# RF_TransimpedanceAmp_FDS02.net
KiCad netlist of a schematic drawn in EAGLE
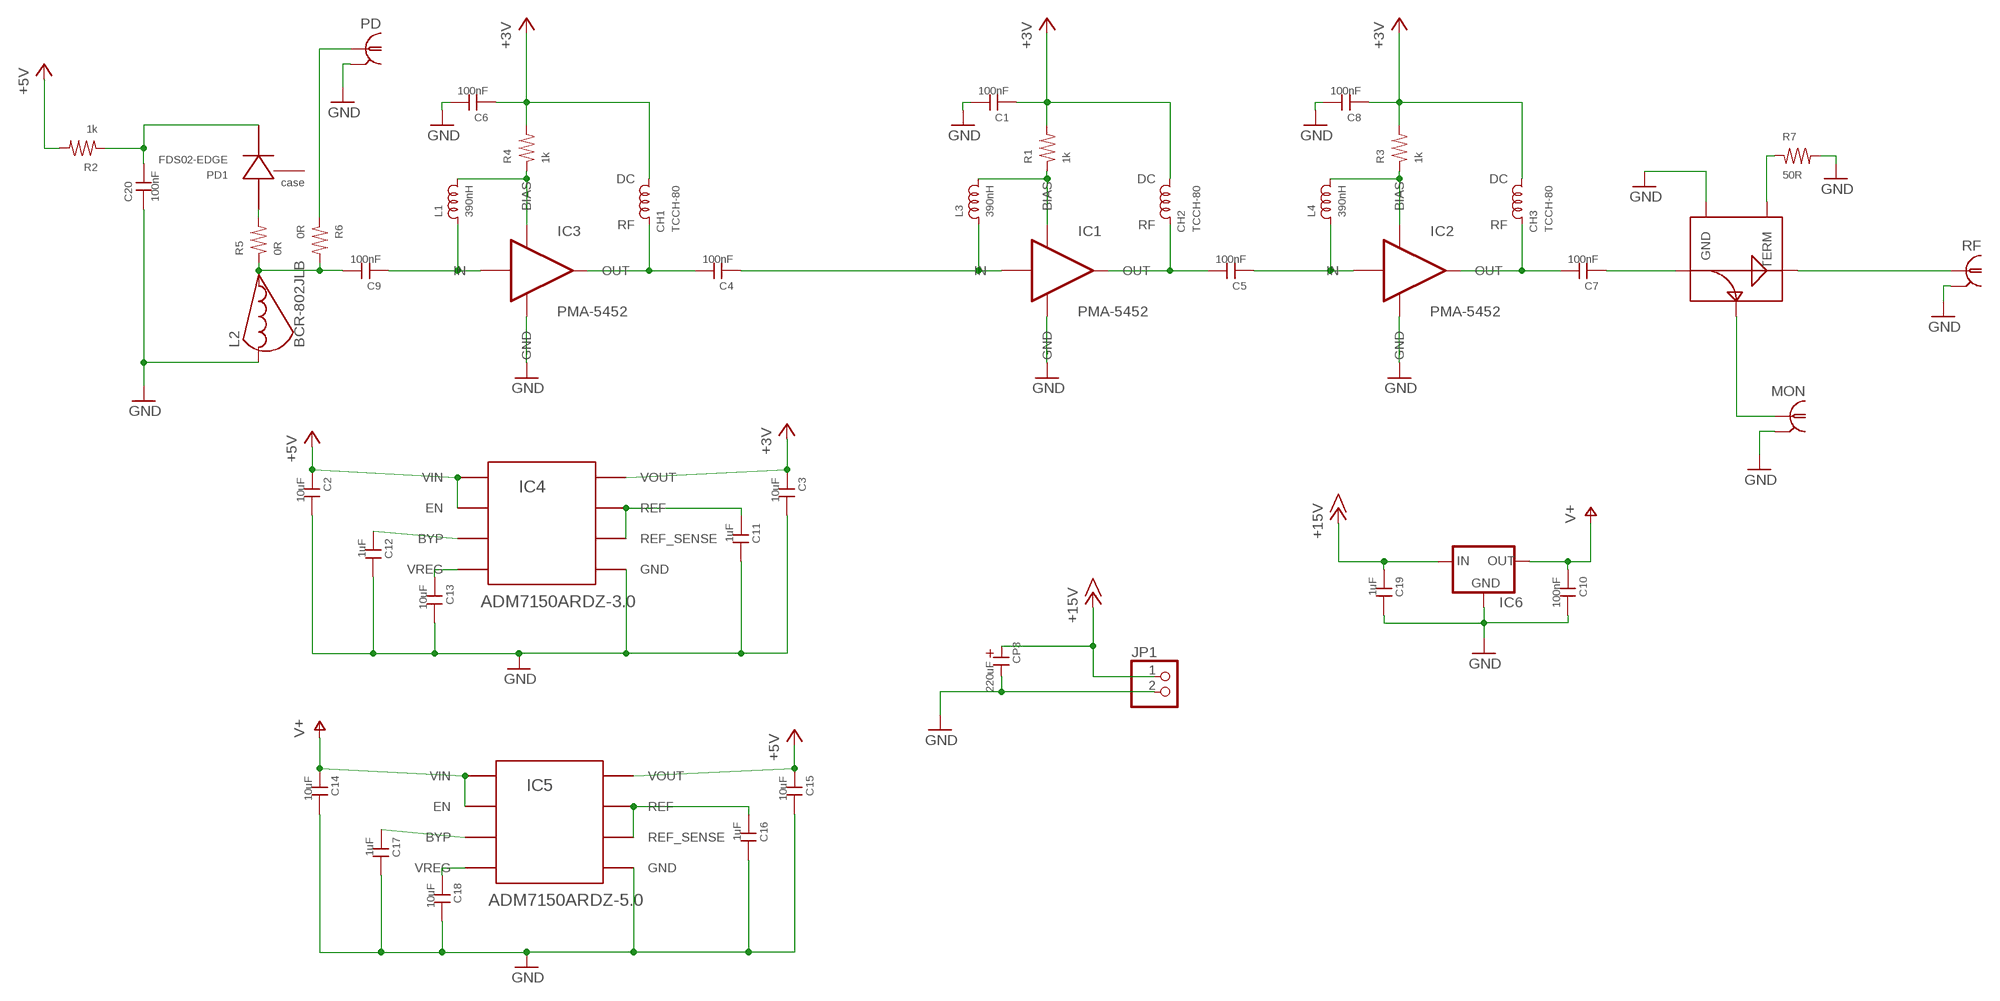
[diagram p0: schematic, sheet 1]

(export (version "E")
  (design (tool "Eeschema 10.0.6"))
  (components
    (comp (ref "C1")
      (value "100nF")
      (footprint "eagle-import:0402")
      (libsource (lib "eagle-import") (part "CAP0402"))
    )
    (comp (ref "C2")
      (value "10uF")
      (footprint "eagle-import:1210")
      (libsource (lib "eagle-import") (part "CAP1210"))
    )
    (comp (ref "C3")
      (value "10uF")
      (footprint "eagle-import:1210")
      (libsource (lib "eagle-import") (part "CAP1210"))
    )
    (comp (ref "C4")
      (value "100nF")
      (footprint "eagle-import:0402")
      (libsource (lib "eagle-import") (part "CAP0402"))
    )
    (comp (ref "C5")
      (value "100nF")
      (footprint "eagle-import:0402")
      (libsource (lib "eagle-import") (part "CAP0402"))
    )
    (comp (ref "C6")
      (value "100nF")
      (footprint "eagle-import:0402")
      (libsource (lib "eagle-import") (part "CAP0402"))
    )
    (comp (ref "C7")
      (value "100nF")
      (footprint "eagle-import:0402")
      (libsource (lib "eagle-import") (part "CAP0402"))
    )
    (comp (ref "C8")
      (value "100nF")
      (footprint "eagle-import:0402")
      (libsource (lib "eagle-import") (part "CAP0402"))
    )
    (comp (ref "C9")
      (value "100nF")
      (footprint "eagle-import:0402")
      (libsource (lib "eagle-import") (part "CAP0402"))
    )
    (comp (ref "C10")
      (value "100nF")
      (footprint "eagle-import:0603")
      (libsource (lib "eagle-import") (part "CAP0603"))
    )
    (comp (ref "C11")
      (value "1uF")
      (footprint "eagle-import:0603")
      (libsource (lib "eagle-import") (part "CAP0603"))
    )
    (comp (ref "C12")
      (value "1uF")
      (footprint "eagle-import:0603")
      (libsource (lib "eagle-import") (part "CAP0603"))
    )
    (comp (ref "C13")
      (value "10uF")
      (footprint "eagle-import:1210")
      (libsource (lib "eagle-import") (part "CAP1210"))
    )
    (comp (ref "C14")
      (value "10uF")
      (footprint "eagle-import:1210")
      (libsource (lib "eagle-import") (part "CAP1210"))
    )
    (comp (ref "C15")
      (value "10uF")
      (footprint "eagle-import:1210")
      (libsource (lib "eagle-import") (part "CAP1210"))
    )
    (comp (ref "C16")
      (value "1uF")
      (footprint "eagle-import:0603")
      (libsource (lib "eagle-import") (part "CAP0603"))
    )
    (comp (ref "C17")
      (value "1uF")
      (footprint "eagle-import:0603")
      (libsource (lib "eagle-import") (part "CAP0603"))
    )
    (comp (ref "C18")
      (value "10uF")
      (footprint "eagle-import:1210")
      (libsource (lib "eagle-import") (part "CAP1210"))
    )
    (comp (ref "C19")
      (value "1uF")
      (footprint "eagle-import:0603")
      (libsource (lib "eagle-import") (part "CAP0603"))
    )
    (comp (ref "C20")
      (value "100nF")
      (footprint "eagle-import:0402")
      (libsource (lib "eagle-import") (part "CAP0402"))
    )
    (comp (ref "CH1")
      (value "TCCH-80")
      (footprint "eagle-import:GU1604")
      (libsource (lib "eagle-import") (part "TCCH-80"))
    )
    (comp (ref "CH2")
      (value "TCCH-80")
      (footprint "eagle-import:GU1604")
      (libsource (lib "eagle-import") (part "TCCH-80"))
    )
    (comp (ref "CH3")
      (value "TCCH-80")
      (footprint "eagle-import:GU1604")
      (libsource (lib "eagle-import") (part "TCCH-80"))
    )
    (comp (ref "CP3")
      (value "220uF")
      (footprint "eagle-import:PANASONIC_F")
      (libsource (lib "eagle-import") (part "CAP-POLPANASONIC_F"))
    )
    (comp (ref "IC1")
      (value "PMA-5452")
      (footprint "eagle-import:DQ849")
      (libsource (lib "eagle-import") (part "PMA-5452"))
    )
    (comp (ref "IC2")
      (value "PMA-5452")
      (footprint "eagle-import:DQ849")
      (libsource (lib "eagle-import") (part "PMA-5452"))
    )
    (comp (ref "IC3")
      (value "PMA-5452")
      (footprint "eagle-import:DQ849")
      (libsource (lib "eagle-import") (part "PMA-5452"))
    )
    (comp (ref "IC4")
      (value "ADM7150ARDZ-3.0")
      (footprint "eagle-import:SO08")
      (libsource (lib "eagle-import") (part "ADM7150"))
    )
    (comp (ref "IC5")
      (value "ADM7150ARDZ-5.0")
      (footprint "eagle-import:SO08")
      (libsource (lib "eagle-import") (part "ADM7150"))
    )
    (comp (ref "IC6")
      (value "78XX-TO220")
      (footprint "eagle-import:TO220")
      (libsource (lib "eagle-import") (part "78XX-TO220"))
    )
    (comp (ref "JP1")
      (value "PINHD-1X2")
      (footprint "eagle-import:1X02")
      (libsource (lib "eagle-import") (part "PINHD-1X2"))
    )
    (comp (ref "L1")
      (value "390nH")
      (footprint "eagle-import:0402")
      (libsource (lib "eagle-import") (part "INDUCTOR-0402"))
    )
    (comp (ref "L2")
      (value "BCR-802JLB")
      (footprint "eagle-import:BCR-MED")
      (libsource (lib "eagle-import") (part "BCR-802JLB"))
    )
    (comp (ref "L3")
      (value "390nH")
      (footprint "eagle-import:0402")
      (libsource (lib "eagle-import") (part "INDUCTOR-0402"))
    )
    (comp (ref "L4")
      (value "390nH")
      (footprint "eagle-import:0402")
      (libsource (lib "eagle-import") (part "INDUCTOR-0402"))
    )
    (comp (ref "MON")
      (value "SMAJ502-bulkhead")
      (footprint "eagle-import:SMA-EDGE")
      (fields (field (name "PARTNO") "CONSMA006.062-ND"))
      (libsource (lib "eagle-import") (part "SMAJ502"))
    )
    (comp (ref "PD")
      (value "SMAJ502-bulkhead")
      (footprint "eagle-import:SMA-EDGE")
      (fields (field (name "PARTNO") "CONSMA006.062-ND"))
      (libsource (lib "eagle-import") (part "SMAJ502"))
    )
    (comp (ref "PD1")
      (value "FDS02-EDGE")
      (footprint "eagle-import:FDS02-SIDEMOUNT")
      (libsource (lib "eagle-import") (part "FDS02-EDGE"))
    )
    (comp (ref "R1")
      (value "1k")
      (footprint "eagle-import:0402")
      (libsource (lib "eagle-import") (part "RES0402"))
    )
    (comp (ref "R2")
      (value "1k")
      (footprint "eagle-import:0402")
      (libsource (lib "eagle-import") (part "RES0402"))
    )
    (comp (ref "R3")
      (value "1k")
      (footprint "eagle-import:0402")
      (libsource (lib "eagle-import") (part "RES0402"))
    )
    (comp (ref "R4")
      (value "1k")
      (footprint "eagle-import:0402")
      (libsource (lib "eagle-import") (part "RES0402"))
    )
    (comp (ref "R5")
      (value "0R")
      (footprint "eagle-import:0402")
      (libsource (lib "eagle-import") (part "RES0402"))
    )
    (comp (ref "R6")
      (value "0R")
      (footprint "eagle-import:0402")
      (libsource (lib "eagle-import") (part "RES0402"))
    )
    (comp (ref "R7")
      (value "50R")
      (footprint "eagle-import:0603")
      (libsource (lib "eagle-import") (part "RES0603"))
    )
    (comp (ref "RF")
      (value "SMAJ502")
      (footprint "eagle-import:SMA-EDGE")
      (libsource (lib "eagle-import") (part "SMAJ502"))
    )
    (comp (ref "U$1")
      (value "ADC-10-4")
      (footprint "eagle-import:BH292")
      (libsource (lib "eagle-import") (part "ADC-10-4"))
    )
  )
  (nets
    (net (code "1") (name "+3V") (class "Default")
      (node (ref "C1") (pin "1") (pinfunction "P$1_1") (pintype "passive"))
      (node (ref "C3") (pin "1") (pinfunction "P$1_1") (pintype "passive"))
      (node (ref "C6") (pin "1") (pinfunction "P$1_1") (pintype "passive"))
      (node (ref "C8") (pin "1") (pinfunction "P$1_1") (pintype "passive"))
      (node (ref "CH1") (pin "P$3") (pinfunction "DC_P$3") (pintype "passive"))
      (node (ref "CH2") (pin "P$3") (pinfunction "DC_P$3") (pintype "passive"))
      (node (ref "CH3") (pin "P$3") (pinfunction "DC_P$3") (pintype "passive"))
      (node (ref "IC4") (pin "2") (pinfunction "VOUT_2") (pintype "bidirectional"))
      (node (ref "R1") (pin "2") (pinfunction "P$2_2") (pintype "passive"))
      (node (ref "R3") (pin "2") (pinfunction "P$2_2") (pintype "passive"))
      (node (ref "R4") (pin "2") (pinfunction "P$2_2") (pintype "passive"))
    )
    (net (code "2") (name "+5V") (class "Default")
      (node (ref "C15") (pin "1") (pinfunction "P$1_1") (pintype "passive"))
      (node (ref "C2") (pin "1") (pinfunction "P$1_1") (pintype "passive"))
      (node (ref "IC4") (pin "7") (pinfunction "EN_7") (pintype "bidirectional"))
      (node (ref "IC4") (pin "8") (pinfunction "VIN_8") (pintype "bidirectional"))
      (node (ref "IC5") (pin "2") (pinfunction "VOUT_2") (pintype "bidirectional"))
      (node (ref "R2") (pin "2") (pinfunction "P$2_2") (pintype "passive"))
    )
    (net (code "3") (name "+15V") (class "Default")
      (node (ref "C19") (pin "1") (pinfunction "P$1_1") (pintype "passive"))
      (node (ref "CP3") (pin "+") (pinfunction "P$1_+") (pintype "passive"))
      (node (ref "IC6") (pin "1") (pinfunction "IN_1") (pintype "input"))
      (node (ref "JP1") (pin "1") (pinfunction "1_1") (pintype "passive"))
    )
    (net (code "4") (name "GND") (class "Default")
      (node (ref "C1") (pin "2") (pinfunction "P$2_2") (pintype "passive"))
      (node (ref "C10") (pin "2") (pinfunction "P$2_2") (pintype "passive"))
      (node (ref "C11") (pin "2") (pinfunction "P$2_2") (pintype "passive"))
      (node (ref "C12") (pin "2") (pinfunction "P$2_2") (pintype "passive"))
      (node (ref "C13") (pin "2") (pinfunction "P$2_2") (pintype "passive"))
      (node (ref "C14") (pin "2") (pinfunction "P$2_2") (pintype "passive"))
      (node (ref "C15") (pin "2") (pinfunction "P$2_2") (pintype "passive"))
      (node (ref "C16") (pin "2") (pinfunction "P$2_2") (pintype "passive"))
      (node (ref "C17") (pin "2") (pinfunction "P$2_2") (pintype "passive"))
      (node (ref "C18") (pin "2") (pinfunction "P$2_2") (pintype "passive"))
      (node (ref "C19") (pin "2") (pinfunction "P$2_2") (pintype "passive"))
      (node (ref "C2") (pin "2") (pinfunction "P$2_2") (pintype "passive"))
      (node (ref "C20") (pin "1") (pinfunction "P$1_1") (pintype "passive"))
      (node (ref "C3") (pin "2") (pinfunction "P$2_2") (pintype "passive"))
      (node (ref "C6") (pin "2") (pinfunction "P$2_2") (pintype "passive"))
      (node (ref "C8") (pin "2") (pinfunction "P$2_2") (pintype "passive"))
      (node (ref "CP3") (pin "-") (pinfunction "P$2_-") (pintype "passive"))
      (node (ref "IC1") (pin "P$GND") (pinfunction "GND_P$GND") (pintype "power_in"))
      (node (ref "IC2") (pin "P$GND") (pinfunction "GND_P$GND") (pintype "power_in"))
      (node (ref "IC3") (pin "P$GND") (pinfunction "GND_P$GND") (pintype "power_in"))
      (node (ref "IC4") (pin "4") (pinfunction "GND_4") (pintype "bidirectional"))
      (node (ref "IC5") (pin "4") (pinfunction "GND_4") (pintype "bidirectional"))
      (node (ref "IC6") (pin "2") (pinfunction "GND_2") (pintype "input"))
      (node (ref "JP1") (pin "2") (pinfunction "2_2") (pintype "passive"))
      (node (ref "L2") (pin "2") (pinfunction "2_2") (pintype "passive"))
      (node (ref "MON") (pin "G@1") (pinfunction "2_G@1") (pintype "passive"))
      (node (ref "MON") (pin "G@2") (pinfunction "2_G@2") (pintype "passive"))
      (node (ref "MON") (pin "G@3") (pinfunction "2_G@3") (pintype "passive"))
      (node (ref "MON") (pin "G@4") (pinfunction "2_G@4") (pintype "passive"))
      (node (ref "PD") (pin "G@1") (pinfunction "2_G@1") (pintype "passive"))
      (node (ref "PD") (pin "G@2") (pinfunction "2_G@2") (pintype "passive"))
      (node (ref "PD") (pin "G@3") (pinfunction "2_G@3") (pintype "passive"))
      (node (ref "PD") (pin "G@4") (pinfunction "2_G@4") (pintype "passive"))
      (node (ref "R7") (pin "2") (pinfunction "P$2_2") (pintype "passive"))
      (node (ref "RF") (pin "G@1") (pinfunction "2_G@1") (pintype "passive"))
      (node (ref "RF") (pin "G@2") (pinfunction "2_G@2") (pintype "passive"))
      (node (ref "RF") (pin "G@3") (pinfunction "2_G@3") (pintype "passive"))
      (node (ref "RF") (pin "G@4") (pinfunction "2_G@4") (pintype "passive"))
      (node (ref "U$1") (pin "P2") (pinfunction "GND_P2") (pintype "bidirectional"))
    )
    (net (code "5") (name "Net-(C4-P$1)") (class "Default")
      (node (ref "C4") (pin "1") (pinfunction "P$1_1") (pintype "passive"))
      (node (ref "IC1") (pin "P$1") (pinfunction "IN_P$1") (pintype "input"))
      (node (ref "L3") (pin "1") (pinfunction "P$1_1") (pintype "passive"))
    )
    (net (code "6") (name "Net-(C4-P$2)") (class "Default")
      (node (ref "C4") (pin "2") (pinfunction "P$2_2") (pintype "passive"))
      (node (ref "CH1") (pin "P$1") (pinfunction "RF_P$1") (pintype "passive"))
      (node (ref "IC3") (pin "P$6") (pinfunction "OUT_P$6") (pintype "output"))
    )
    (net (code "7") (name "Net-(C5-P$1)") (class "Default")
      (node (ref "C5") (pin "1") (pinfunction "P$1_1") (pintype "passive"))
      (node (ref "IC2") (pin "P$1") (pinfunction "IN_P$1") (pintype "input"))
      (node (ref "L4") (pin "1") (pinfunction "P$1_1") (pintype "passive"))
    )
    (net (code "8") (name "Net-(C5-P$2)") (class "Default")
      (node (ref "C5") (pin "2") (pinfunction "P$2_2") (pintype "passive"))
      (node (ref "CH2") (pin "P$1") (pinfunction "RF_P$1") (pintype "passive"))
      (node (ref "IC1") (pin "P$6") (pinfunction "OUT_P$6") (pintype "output"))
    )
    (net (code "9") (name "Net-(C7-P$1)") (class "Default")
      (node (ref "C7") (pin "1") (pinfunction "P$1_1") (pintype "passive"))
      (node (ref "U$1") (pin "P1") (pinfunction "IN_P1") (pintype "bidirectional"))
    )
    (net (code "10") (name "Net-(C7-P$2)") (class "Default")
      (node (ref "C7") (pin "2") (pinfunction "P$2_2") (pintype "passive"))
      (node (ref "CH3") (pin "P$1") (pinfunction "RF_P$1") (pintype "passive"))
      (node (ref "IC2") (pin "P$6") (pinfunction "OUT_P$6") (pintype "output"))
    )
    (net (code "11") (name "Net-(C9-P$1)") (class "Default")
      (node (ref "C9") (pin "1") (pinfunction "P$1_1") (pintype "passive"))
      (node (ref "IC3") (pin "P$1") (pinfunction "IN_P$1") (pintype "input"))
      (node (ref "L1") (pin "1") (pinfunction "P$1_1") (pintype "passive"))
    )
    (net (code "12") (name "Net-(C9-P$2)") (class "Default")
      (node (ref "C9") (pin "2") (pinfunction "P$2_2") (pintype "passive"))
      (node (ref "L2") (pin "1") (pinfunction "1_1") (pintype "passive"))
      (node (ref "R5") (pin "1") (pinfunction "P$1_1") (pintype "passive"))
      (node (ref "R6") (pin "2") (pinfunction "P$2_2") (pintype "passive"))
    )
    (net (code "13") (name "Net-(C11-P$1)") (class "Default")
      (node (ref "C11") (pin "1") (pinfunction "P$1_1") (pintype "passive"))
      (node (ref "IC4") (pin "5") (pinfunction "REF_SENSE_5") (pintype "bidirectional"))
      (node (ref "IC4") (pin "6") (pinfunction "REF_6") (pintype "bidirectional"))
    )
    (net (code "14") (name "Net-(C12-P$1)") (class "Default")
      (node (ref "C12") (pin "1") (pinfunction "P$1_1") (pintype "passive"))
      (node (ref "IC4") (pin "3") (pinfunction "BYP_3") (pintype "bidirectional"))
    )
    (net (code "15") (name "Net-(C13-P$1)") (class "Default")
      (node (ref "C13") (pin "1") (pinfunction "P$1_1") (pintype "passive"))
      (node (ref "IC4") (pin "1") (pinfunction "VREG_1") (pintype "bidirectional"))
    )
    (net (code "16") (name "Net-(C16-P$1)") (class "Default")
      (node (ref "C16") (pin "1") (pinfunction "P$1_1") (pintype "passive"))
      (node (ref "IC5") (pin "5") (pinfunction "REF_SENSE_5") (pintype "bidirectional"))
      (node (ref "IC5") (pin "6") (pinfunction "REF_6") (pintype "bidirectional"))
    )
    (net (code "17") (name "Net-(C17-P$1)") (class "Default")
      (node (ref "C17") (pin "1") (pinfunction "P$1_1") (pintype "passive"))
      (node (ref "IC5") (pin "3") (pinfunction "BYP_3") (pintype "bidirectional"))
    )
    (net (code "18") (name "Net-(C18-P$1)") (class "Default")
      (node (ref "C18") (pin "1") (pinfunction "P$1_1") (pintype "passive"))
      (node (ref "IC5") (pin "1") (pinfunction "VREG_1") (pintype "bidirectional"))
    )
    (net (code "19") (name "Net-(C20-P$2)") (class "Default")
      (node (ref "C20") (pin "2") (pinfunction "P$2_2") (pintype "passive"))
      (node (ref "PD1") (pin "P$1") (pinfunction "CATHODE_P$1") (pintype "bidirectional"))
      (node (ref "R2") (pin "1") (pinfunction "P$1_1") (pintype "passive"))
    )
    (net (code "20") (name "Net-(IC1-BIAS)") (class "Default")
      (node (ref "IC1") (pin "P$7") (pinfunction "BIAS_P$7") (pintype "power_in"))
      (node (ref "L3") (pin "2") (pinfunction "P$2_2") (pintype "passive"))
      (node (ref "R1") (pin "1") (pinfunction "P$1_1") (pintype "passive"))
    )
    (net (code "21") (name "Net-(IC2-BIAS)") (class "Default")
      (node (ref "IC2") (pin "P$7") (pinfunction "BIAS_P$7") (pintype "power_in"))
      (node (ref "L4") (pin "2") (pinfunction "P$2_2") (pintype "passive"))
      (node (ref "R3") (pin "1") (pinfunction "P$1_1") (pintype "passive"))
    )
    (net (code "22") (name "Net-(IC3-BIAS)") (class "Default")
      (node (ref "IC3") (pin "P$7") (pinfunction "BIAS_P$7") (pintype "power_in"))
      (node (ref "L1") (pin "2") (pinfunction "P$2_2") (pintype "passive"))
      (node (ref "R4") (pin "1") (pinfunction "P$1_1") (pintype "passive"))
    )
    (net (code "23") (name "Net-(PD1-ANODE)") (class "Default")
      (node (ref "PD1") (pin "P$3") (pinfunction "ANODE_P$3") (pintype "bidirectional"))
      (node (ref "R5") (pin "2") (pinfunction "P$2_2") (pintype "passive"))
    )
    (net (code "24") (name "Net-(R6-P$1)") (class "Default")
      (node (ref "PD") (pin "1") (pinfunction "1_1") (pintype "passive"))
      (node (ref "R6") (pin "1") (pinfunction "P$1_1") (pintype "passive"))
    )
    (net (code "25") (name "Net-(R7-P$1)") (class "Default")
      (node (ref "R7") (pin "1") (pinfunction "P$1_1") (pintype "passive"))
      (node (ref "U$1") (pin "P4") (pinfunction "TERM_P4") (pintype "bidirectional"))
    )
    (net (code "26") (name "Net-(U$1-COUP)") (class "Default")
      (node (ref "MON") (pin "1") (pinfunction "1_1") (pintype "passive"))
      (node (ref "U$1") (pin "P3") (pinfunction "COUP_P3") (pintype "bidirectional"))
    )
    (net (code "27") (name "Net-(U$1-OUT)") (class "Default")
      (node (ref "RF") (pin "1") (pinfunction "1_1") (pintype "passive"))
      (node (ref "U$1") (pin "P6") (pinfunction "OUT_P6") (pintype "bidirectional"))
    )
    (net (code "28") (name "V+") (class "Default")
      (node (ref "C10") (pin "1") (pinfunction "P$1_1") (pintype "passive"))
      (node (ref "C14") (pin "1") (pinfunction "P$1_1") (pintype "passive"))
      (node (ref "IC5") (pin "7") (pinfunction "EN_7") (pintype "bidirectional"))
      (node (ref "IC5") (pin "8") (pinfunction "VIN_8") (pintype "bidirectional"))
      (node (ref "IC6") (pin "3") (pinfunction "OUT_3") (pintype "passive"))
    )
    (net (code "29") (name "unconnected-(PD1-CASE-PadP$2)") (class "Default")
      (node (ref "PD1") (pin "P$2") (pinfunction "CASE_P$2") (pintype "bidirectional"))
    )
  )
)
